# ROS-Robot-Controller.net
KiCad netlist of a schematic drawn in Altium Designer
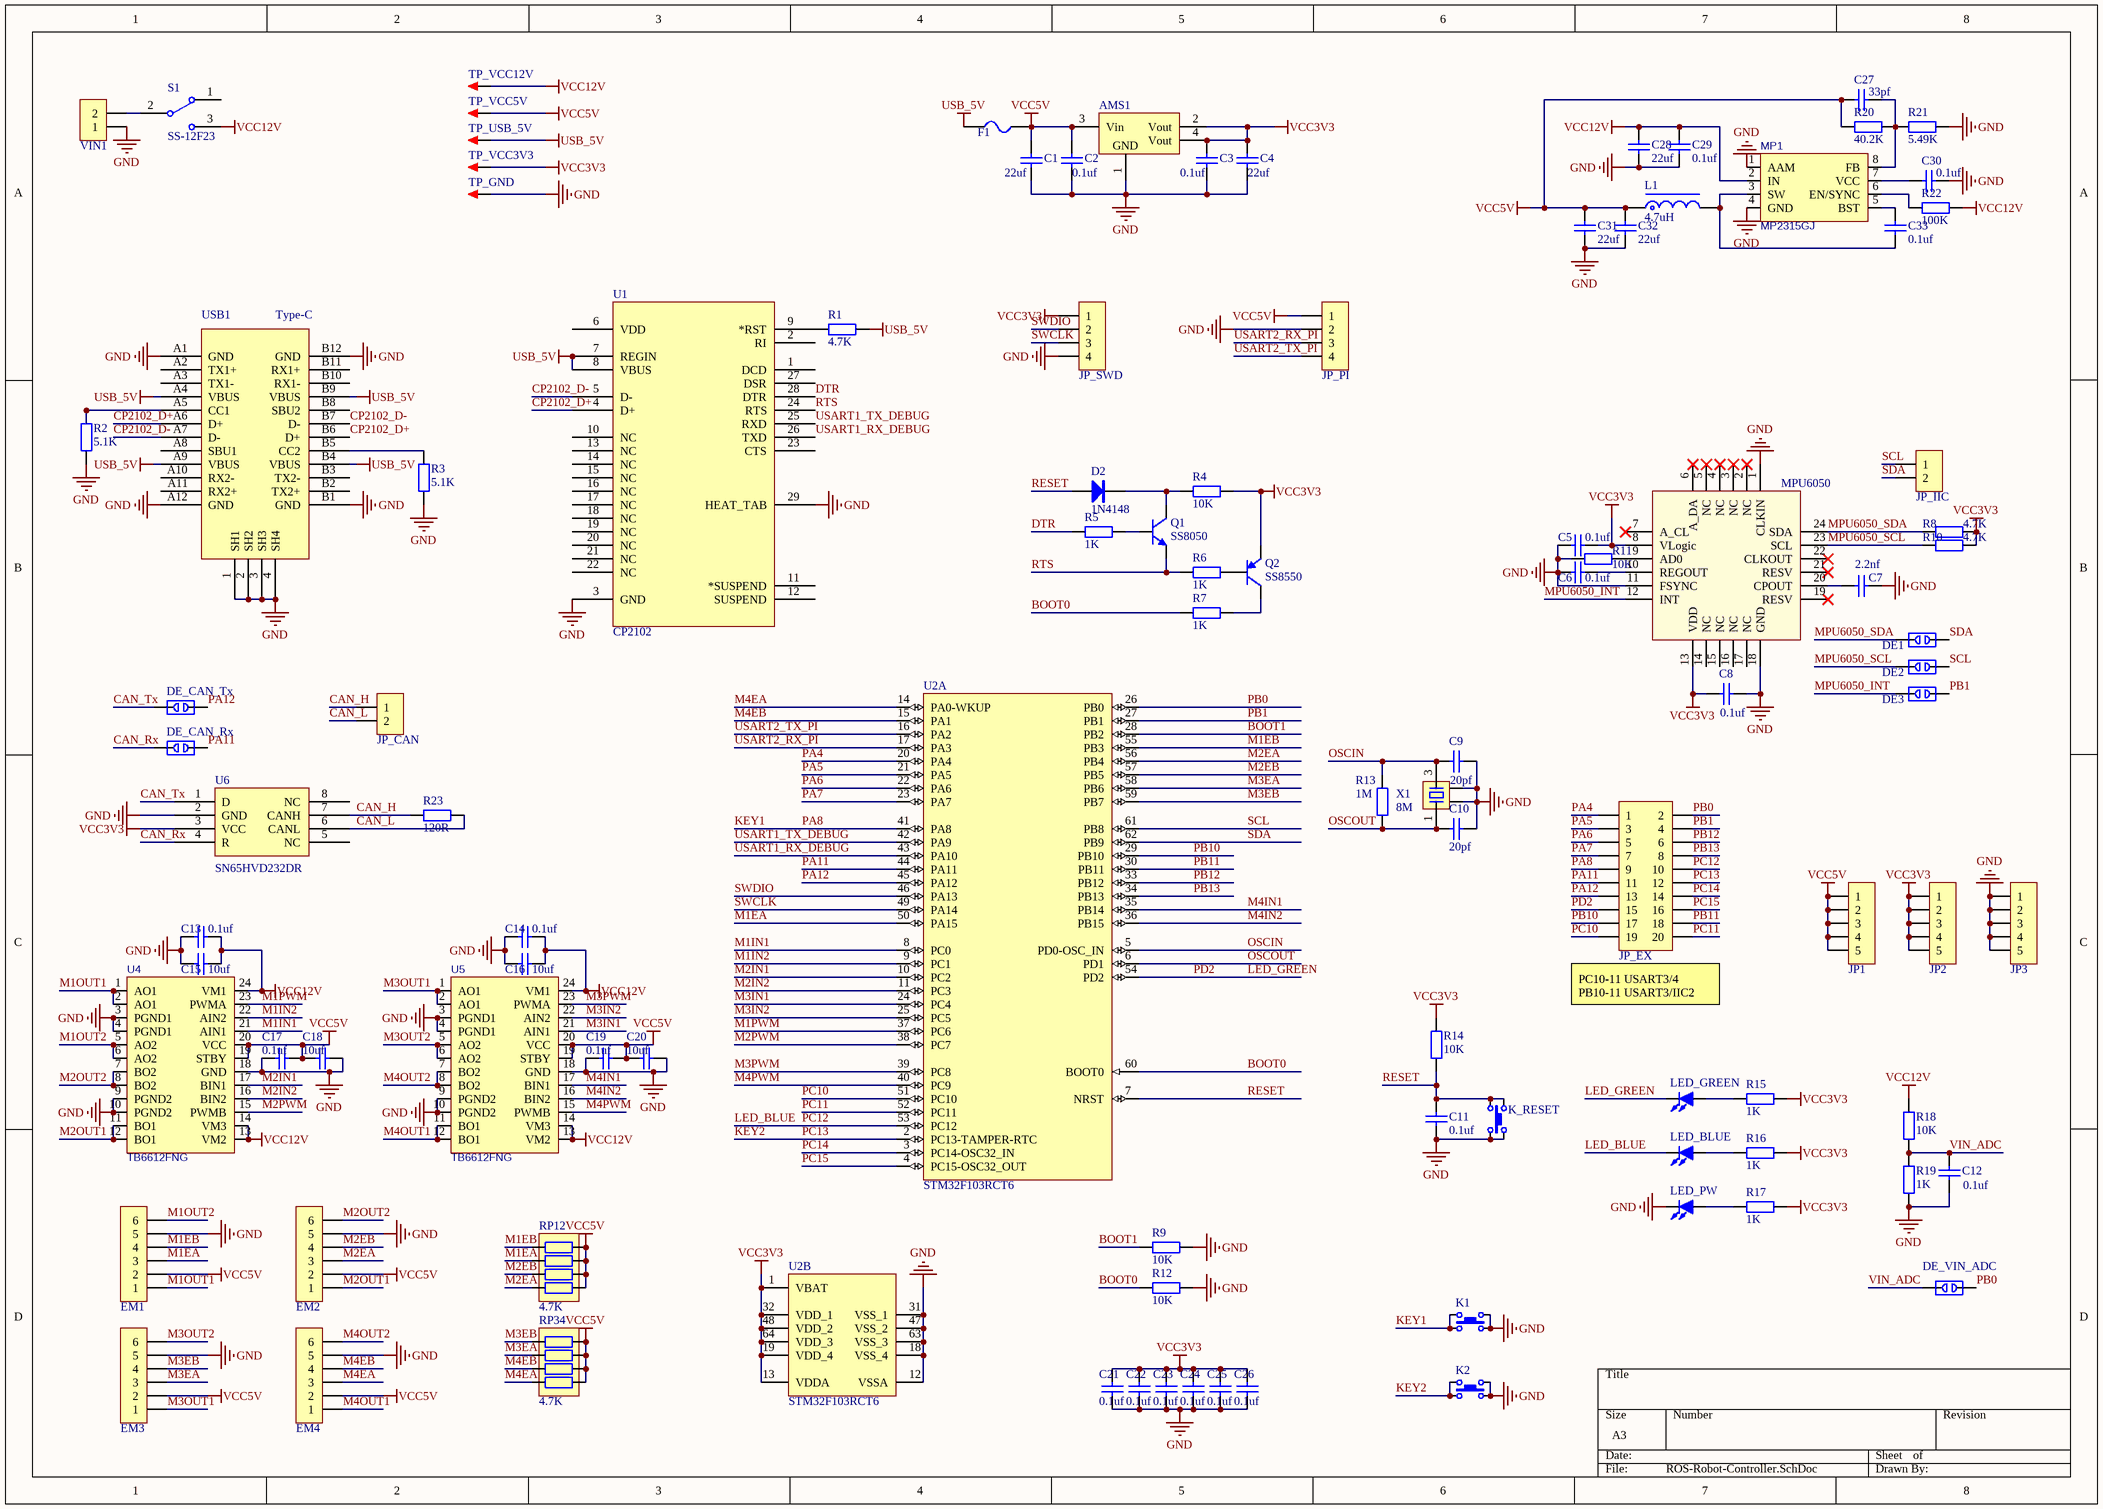
[diagram p0: ROS-Robot-Controller.SchDoc]

(export (version "E")
  (design (tool "Eeschema 10.0.6"))
  (components
    (comp (ref "AMS1")
      (value "AMS1117-3V3")
      (footprint "SOT223_L")
      (description "三端稳压芯片")
      (libsource (lib "1.1 - 电源类芯片") (part "AMS1117"))
    )
    (comp (ref "C1")
      (value "22uf")
      (footprint "C0603_L")
      (description "贴片电容")
      (libsource (lib "0.1 - 电阻-电容-电感-电位器") (part "C"))
    )
    (comp (ref "C2")
      (value "0.1uf")
      (footprint "C0603_L")
      (description "贴片电容")
      (libsource (lib "0.1 - 电阻-电容-电感-电位器") (part "C"))
    )
    (comp (ref "C3")
      (value "0.1uf")
      (footprint "C0603_L")
      (description "贴片电容")
      (libsource (lib "0.1 - 电阻-电容-电感-电位器") (part "C"))
    )
    (comp (ref "C4")
      (value "22uf")
      (footprint "C0603_L")
      (description "贴片电容")
      (libsource (lib "0.1 - 电阻-电容-电感-电位器") (part "C"))
    )
    (comp (ref "C5")
      (value "0.1uf")
      (footprint "C0402_L")
      (description "贴片电容")
      (libsource (lib "0.1 - 电阻-电容-电感-电位器") (part "C"))
    )
    (comp (ref "C6")
      (value "0.1uf")
      (footprint "C0402_L")
      (description "贴片电容")
      (libsource (lib "0.1 - 电阻-电容-电感-电位器") (part "C"))
    )
    (comp (ref "C7")
      (value "2.2nf")
      (footprint "C0402_L")
      (description "贴片电容")
      (libsource (lib "0.1 - 电阻-电容-电感-电位器") (part "C"))
    )
    (comp (ref "C8")
      (value "0.1uf")
      (footprint "C0402_L")
      (description "贴片电容")
      (libsource (lib "0.1 - 电阻-电容-电感-电位器") (part "C"))
    )
    (comp (ref "C9")
      (value "20pf")
      (footprint "C0402_L")
      (description "贴片电容")
      (libsource (lib "0.1 - 电阻-电容-电感-电位器") (part "C"))
    )
    (comp (ref "C10")
      (value "20pf")
      (footprint "C0402_L")
      (description "贴片电容")
      (libsource (lib "0.1 - 电阻-电容-电感-电位器") (part "C"))
    )
    (comp (ref "C11")
      (value "0.1uf")
      (footprint "C0402_L")
      (description "贴片电容")
      (libsource (lib "0.1 - 电阻-电容-电感-电位器") (part "C"))
    )
    (comp (ref "C12")
      (value "0.1uf")
      (footprint "C0603_L")
      (description "贴片电容")
      (libsource (lib "0.1 - 电阻-电容-电感-电位器") (part "C"))
    )
    (comp (ref "C13")
      (value "0.1uf")
      (footprint "C0603_L")
      (description "贴片电容")
      (libsource (lib "0.1 - 电阻-电容-电感-电位器") (part "C"))
    )
    (comp (ref "C14")
      (value "0.1uf")
      (footprint "C0603_L")
      (description "贴片电容")
      (libsource (lib "0.1 - 电阻-电容-电感-电位器") (part "C"))
    )
    (comp (ref "C15")
      (value "10uf")
      (footprint "C0603_L")
      (description "贴片电容")
      (libsource (lib "0.1 - 电阻-电容-电感-电位器") (part "C"))
    )
    (comp (ref "C16")
      (value "10uf")
      (footprint "C0603_L")
      (description "贴片电容")
      (libsource (lib "0.1 - 电阻-电容-电感-电位器") (part "C"))
    )
    (comp (ref "C17")
      (value "0.1uf")
      (footprint "C0402_L")
      (description "贴片电容")
      (libsource (lib "0.1 - 电阻-电容-电感-电位器") (part "C"))
    )
    (comp (ref "C18")
      (value "10uf")
      (footprint "C0402_L")
      (description "贴片电容")
      (libsource (lib "0.1 - 电阻-电容-电感-电位器") (part "C"))
    )
    (comp (ref "C19")
      (value "0.1uf")
      (footprint "C0402_L")
      (description "贴片电容")
      (libsource (lib "0.1 - 电阻-电容-电感-电位器") (part "C"))
    )
    (comp (ref "C20")
      (value "10uf")
      (footprint "C0402_L")
      (description "贴片电容")
      (libsource (lib "0.1 - 电阻-电容-电感-电位器") (part "C"))
    )
    (comp (ref "C21")
      (value "0.1uf")
      (footprint "C0402_L")
      (description "贴片电容")
      (libsource (lib "0.1 - 电阻-电容-电感-电位器") (part "C"))
    )
    (comp (ref "C22")
      (value "0.1uf")
      (footprint "C0402_L")
      (description "贴片电容")
      (libsource (lib "0.1 - 电阻-电容-电感-电位器") (part "C"))
    )
    (comp (ref "C23")
      (value "0.1uf")
      (footprint "C0402_L")
      (description "贴片电容")
      (libsource (lib "0.1 - 电阻-电容-电感-电位器") (part "C"))
    )
    (comp (ref "C24")
      (value "0.1uf")
      (footprint "C0402_L")
      (description "贴片电容")
      (libsource (lib "0.1 - 电阻-电容-电感-电位器") (part "C"))
    )
    (comp (ref "C25")
      (value "0.1uf")
      (footprint "C0402_L")
      (description "贴片电容")
      (libsource (lib "0.1 - 电阻-电容-电感-电位器") (part "C"))
    )
    (comp (ref "C26")
      (value "0.1uf")
      (footprint "C0402_L")
      (description "贴片电容")
      (libsource (lib "0.1 - 电阻-电容-电感-电位器") (part "C"))
    )
    (comp (ref "C27")
      (value "33pf")
      (footprint "C0603_L")
      (description "贴片电容")
      (libsource (lib "0.1 - 电阻-电容-电感-电位器") (part "C"))
    )
    (comp (ref "C28")
      (value "22uf")
      (footprint "C0805_L")
      (description "贴片电容")
      (libsource (lib "0.1 - 电阻-电容-电感-电位器") (part "C"))
    )
    (comp (ref "C29")
      (value "0.1uf")
      (footprint "C0805_L")
      (description "贴片电容")
      (libsource (lib "0.1 - 电阻-电容-电感-电位器") (part "C"))
    )
    (comp (ref "C30")
      (value "0.1uf")
      (footprint "C0603_L")
      (description "贴片电容")
      (libsource (lib "0.1 - 电阻-电容-电感-电位器") (part "C"))
    )
    (comp (ref "C31")
      (value "22uf")
      (footprint "C0603_L")
      (description "贴片电容")
      (libsource (lib "0.1 - 电阻-电容-电感-电位器") (part "C"))
    )
    (comp (ref "C32")
      (value "22uf")
      (footprint "C0603_L")
      (description "贴片电容")
      (libsource (lib "0.1 - 电阻-电容-电感-电位器") (part "C"))
    )
    (comp (ref "C33")
      (value "0.1uf")
      (footprint "C0603_L")
      (description "贴片电容")
      (libsource (lib "0.1 - 电阻-电容-电感-电位器") (part "C"))
    )
    (comp (ref "D2")
      (value "1N4148")
      (footprint "SOD-323")
      (description "开关二极管")
      (libsource (lib "0.2 - 二极管-TVS-整流桥") (part "1N4148"))
    )
    (comp (ref "DE1")
      (value "DEBUG PAD")
      (footprint "DEBUG_B")
      (description "调试断点焊盘")
      (libsource (lib "0.7 - 常用按键-开关-蜂鸣器-电池-测试点") (part "DEBUG"))
    )
    (comp (ref "DE2")
      (value "DEBUG PAD")
      (footprint "DEBUG_B")
      (description "调试断点焊盘")
      (libsource (lib "0.7 - 常用按键-开关-蜂鸣器-电池-测试点") (part "DEBUG"))
    )
    (comp (ref "DE3")
      (value "DEBUG PAD")
      (footprint "DEBUG_B")
      (description "调试断点焊盘")
      (libsource (lib "0.7 - 常用按键-开关-蜂鸣器-电池-测试点") (part "DEBUG"))
    )
    (comp (ref "DE_CAN_Rx")
      (value "DEBUG PAD")
      (footprint "DEBUG_B")
      (description "调试断点焊盘")
      (libsource (lib "0.7 - 常用按键-开关-蜂鸣器-电池-测试点") (part "DEBUG"))
    )
    (comp (ref "DE_CAN_Tx")
      (value "DEBUG PAD")
      (footprint "DEBUG_B")
      (description "调试断点焊盘")
      (libsource (lib "0.7 - 常用按键-开关-蜂鸣器-电池-测试点") (part "DEBUG"))
    )
    (comp (ref "DE_VIN_ADC")
      (value "DEBUG PAD")
      (footprint "DEBUG_B")
      (description "调试断点焊盘")
      (libsource (lib "0.7 - 常用按键-开关-蜂鸣器-电池-测试点") (part "DEBUG"))
    )
    (comp (ref "EM1")
      (value "HDR-1X6")
      (footprint "PH2.0-LI-6P")
      (description "6P接插件")
      (libsource (lib "5.3 - 接插件-脚距2.0") (part "Header 6"))
    )
    (comp (ref "EM2")
      (value "HDR-1X6")
      (footprint "PH2.0-LI-6P")
      (description "6P接插件")
      (libsource (lib "5.3 - 接插件-脚距2.0") (part "Header 6"))
    )
    (comp (ref "EM3")
      (value "HDR-1X6")
      (footprint "PH2.0-LI-6P")
      (description "6P接插件")
      (libsource (lib "5.3 - 接插件-脚距2.0") (part "Header 6"))
    )
    (comp (ref "EM4")
      (value "HDR-1X6")
      (footprint "PH2.0-LI-6P")
      (description "6P接插件")
      (libsource (lib "5.3 - 接插件-脚距2.0") (part "Header 6"))
    )
    (comp (ref "F1")
      (value "MSMD200-8V 2A")
      (footprint "FU 0603")
      (description "贴片保险丝")
      (libsource (lib "0.5 - 保险丝-晶振-光耦") (part "FU"))
    )
    (comp (ref "JP1")
      (value "HDR-1X5")
      (footprint "HDR2.54-LI-5P")
      (description "5P接插件")
      (libsource (lib "5.4 - 接插件-脚距2.54 (100mil) ") (part "Header 5"))
    )
    (comp (ref "JP2")
      (value "HDR-1X5")
      (footprint "HDR2.54-LI-5P")
      (description "5P接插件")
      (libsource (lib "5.4 - 接插件-脚距2.54 (100mil) ") (part "Header 5"))
    )
    (comp (ref "JP3")
      (value "HDR-1X5")
      (footprint "HDR2.54-LI-5P")
      (description "5P接插件")
      (libsource (lib "5.4 - 接插件-脚距2.54 (100mil) ") (part "Header 5"))
    )
    (comp (ref "JP_CAN")
      (value "HDR-1X2")
      (footprint "XH2.54-WI-2P")
      (description "2P接插件")
      (libsource (lib "5.4 - 接插件-脚距2.54 (100mil) ") (part "Header 2"))
    )
    (comp (ref "JP_EX")
      (value "Header 2X10")
      (footprint "IDC2.54-LI-2x10P")
      (description "10*2P接插件")
      (libsource (lib "5.4 - 接插件-脚距2.54 (100mil) ") (part "Header 10X2"))
    )
    (comp (ref "JP_IIC")
      (value "HDR-1X2")
      (footprint "XH2.54-WI-2P")
      (description "2P接插件")
      (libsource (lib "5.4 - 接插件-脚距2.54 (100mil) ") (part "Header 2"))
    )
    (comp (ref "JP_PI")
      (value "HDR-1X4")
      (footprint "HDR2.54-LI-4P")
      (description "4P接插件")
      (libsource (lib "5.4 - 接插件-脚距2.54 (100mil) ") (part "Header 4"))
    )
    (comp (ref "JP_SWD")
      (value "HDR-1X4")
      (footprint "XH2.54-WI-4P")
      (description "4P接插件")
      (libsource (lib "5.4 - 接插件-脚距2.54 (100mil) ") (part "Header 4"))
    )
    (comp (ref "K1")
      (value "TACT 4P")
      (footprint "SW-SMD_4P-L4.2-W3.3-P2.15-LS5.1")
      (description "Button")
      (libsource (lib "KitSprout") (part "ButtonTACT"))
    )
    (comp (ref "K2")
      (value "TACT 4P")
      (footprint "SW-SMD_4P-L4.2-W3.3-P2.15-LS5.1")
      (description "Button")
      (libsource (lib "KitSprout") (part "ButtonTACT"))
    )
    (comp (ref "K_RESET")
      (value "TACT 4P")
      (footprint "SW-SMD_4P-L4.2-W3.3-P2.15-LS5.1")
      (description "Button")
      (libsource (lib "KitSprout") (part "ButtonTACT"))
    )
    (comp (ref "L1")
      (value "4.7uH")
      (footprint "L-SMD-0420")
      (description "一体成型电感")
      (libsource (lib "0.1 - 电阻-电容-电感-电位器") (part "L-Molding Choke"))
    )
    (comp (ref "LED_BLUE")
      (value "红色")
      (footprint "LED_0402_RED")
      (description "贴片LED")
      (libsource (lib "0.3 - LED发光二极管") (part "LED-SMD"))
    )
    (comp (ref "LED_GREEN")
      (value "红色")
      (footprint "LED_0402_RED")
      (description "贴片LED")
      (libsource (lib "0.3 - LED发光二极管") (part "LED-SMD"))
    )
    (comp (ref "LED_PW")
      (value "红色")
      (footprint "LED_0402_RED")
      (description "贴片LED")
      (libsource (lib "0.3 - LED发光二极管") (part "LED-SMD"))
    )
    (comp (ref "MP1")
      (value "MP2315GJ")
      (footprint "SOT23-8N")
      (description "3A/24V DC-DC降压芯片")
      (libsource (lib "1.1 - 电源类芯片") (part "MP2315"))
    )
    (comp (ref "Q1")
      (value "SS8050")
      (footprint "SOT23-3N")
      (description "高频放大-NPN型")
      (libsource (lib "0.4 - 三极管-场效应管-可控硅") (part "8050-SMD"))
    )
    (comp (ref "Q2")
      (value "SS8550")
      (footprint "SOT23-3N")
      (description "高频放大-PNP型")
      (libsource (lib "0.4 - 三极管-场效应管-可控硅") (part "8550-SMD"))
    )
    (comp (ref "R1")
      (value "4.7K")
      (footprint "R0402_L")
      (description "贴片电阻")
      (libsource (lib "0.1 - 电阻-电容-电感-电位器") (part "R"))
    )
    (comp (ref "R2")
      (value "5.1K")
      (footprint "R0402_L")
      (description "贴片电阻")
      (libsource (lib "0.1 - 电阻-电容-电感-电位器") (part "R"))
    )
    (comp (ref "R3")
      (value "5.1K")
      (footprint "R0402_L")
      (description "贴片电阻")
      (libsource (lib "0.1 - 电阻-电容-电感-电位器") (part "R"))
    )
    (comp (ref "R4")
      (value "10K")
      (footprint "R0402_L")
      (description "贴片电阻")
      (libsource (lib "0.1 - 电阻-电容-电感-电位器") (part "R"))
    )
    (comp (ref "R5")
      (value "1K")
      (footprint "R0402_L")
      (description "贴片电阻")
      (libsource (lib "0.1 - 电阻-电容-电感-电位器") (part "R"))
    )
    (comp (ref "R6")
      (value "1K")
      (footprint "R0402_L")
      (description "贴片电阻")
      (libsource (lib "0.1 - 电阻-电容-电感-电位器") (part "R"))
    )
    (comp (ref "R7")
      (value "1K")
      (footprint "R0402_L")
      (description "贴片电阻")
      (libsource (lib "0.1 - 电阻-电容-电感-电位器") (part "R"))
    )
    (comp (ref "R8")
      (value "4.7K")
      (footprint "R0402_L")
      (description "贴片电阻")
      (libsource (lib "0.1 - 电阻-电容-电感-电位器") (part "R"))
    )
    (comp (ref "R9")
      (value "10K")
      (footprint "R0402_L")
      (description "贴片电阻")
      (libsource (lib "0.1 - 电阻-电容-电感-电位器") (part "R"))
    )
    (comp (ref "R10")
      (value "4.7K")
      (footprint "R0402_L")
      (description "贴片电阻")
      (libsource (lib "0.1 - 电阻-电容-电感-电位器") (part "R"))
    )
    (comp (ref "R11")
      (value "10K")
      (footprint "R0402_L")
      (description "贴片电阻")
      (libsource (lib "0.1 - 电阻-电容-电感-电位器") (part "R"))
    )
    (comp (ref "R12")
      (value "10K")
      (footprint "R0402_L")
      (description "贴片电阻")
      (libsource (lib "0.1 - 电阻-电容-电感-电位器") (part "R"))
    )
    (comp (ref "R13")
      (value "1M")
      (footprint "R0402_L")
      (description "贴片电阻")
      (libsource (lib "0.1 - 电阻-电容-电感-电位器") (part "R"))
    )
    (comp (ref "R14")
      (value "10K")
      (footprint "R0402_L")
      (description "贴片电阻")
      (libsource (lib "0.1 - 电阻-电容-电感-电位器") (part "R"))
    )
    (comp (ref "R15")
      (value "1K")
      (footprint "R0402_L")
      (description "贴片电阻")
      (libsource (lib "0.1 - 电阻-电容-电感-电位器") (part "R"))
    )
    (comp (ref "R16")
      (value "1K")
      (footprint "R0402_L")
      (description "贴片电阻")
      (libsource (lib "0.1 - 电阻-电容-电感-电位器") (part "R"))
    )
    (comp (ref "R17")
      (value "1K")
      (footprint "R0402_L")
      (description "贴片电阻")
      (libsource (lib "0.1 - 电阻-电容-电感-电位器") (part "R"))
    )
    (comp (ref "R18")
      (value "10K")
      (footprint "R0603_L")
      (description "贴片电阻")
      (libsource (lib "0.1 - 电阻-电容-电感-电位器") (part "R"))
    )
    (comp (ref "R19")
      (value "1K")
      (footprint "R0603_L")
      (description "贴片电阻")
      (libsource (lib "0.1 - 电阻-电容-电感-电位器") (part "R"))
    )
    (comp (ref "R20")
      (value "40.2K")
      (footprint "R0603_L")
      (description "贴片电阻")
      (libsource (lib "0.1 - 电阻-电容-电感-电位器") (part "R"))
    )
    (comp (ref "R21")
      (value "5.49K")
      (footprint "R0603_L")
      (description "贴片电阻")
      (libsource (lib "0.1 - 电阻-电容-电感-电位器") (part "R"))
    )
    (comp (ref "R22")
      (value "100K")
      (footprint "R0603_L")
      (description "贴片电阻")
      (libsource (lib "0.1 - 电阻-电容-电感-电位器") (part "R"))
    )
    (comp (ref "R23")
      (value "120R")
      (footprint "R0402_L")
      (description "贴片电阻")
      (libsource (lib "0.1 - 电阻-电容-电感-电位器") (part "R"))
    )
    (comp (ref "RP12")
      (value "4.7K")
      (footprint "RCA-8P4R-0402")
      (description "贴片4P排阻")
      (libsource (lib "0.1 - 电阻-电容-电感-电位器") (part "R-8P4R"))
    )
    (comp (ref "RP34")
      (value "4.7K")
      (footprint "RCA-8P4R-0402")
      (description "贴片4P排阻")
      (libsource (lib "0.1 - 电阻-电容-电感-电位器") (part "R-8P4R"))
    )
    (comp (ref "S1")
      (value "SS-12F23")
      (footprint "SS-12D10")
      (description "1路波动开关")
      (libsource (lib "0.7 - 常用按键-开关-蜂鸣器-电池-测试点") (part "SSW-1P"))
    )
    (comp (ref "TP_GND")
      (value "TEST")
      (footprint "TEST 1")
      (description "测试点")
      (libsource (lib "0.7 - 常用按键-开关-蜂鸣器-电池-测试点") (part "TEST"))
    )
    (comp (ref "TP_USB_5V")
      (value "TEST")
      (footprint "TEST 1")
      (description "测试点")
      (libsource (lib "0.7 - 常用按键-开关-蜂鸣器-电池-测试点") (part "TEST"))
    )
    (comp (ref "TP_VCC3V3")
      (value "TEST")
      (footprint "TEST 1")
      (description "测试点")
      (libsource (lib "0.7 - 常用按键-开关-蜂鸣器-电池-测试点") (part "TEST"))
    )
    (comp (ref "TP_VCC5V")
      (value "TEST")
      (footprint "TEST 1")
      (description "测试点")
      (libsource (lib "0.7 - 常用按键-开关-蜂鸣器-电池-测试点") (part "TEST"))
    )
    (comp (ref "TP_VCC12V")
      (value "TEST")
      (footprint "TEST 1")
      (description "测试点")
      (libsource (lib "0.7 - 常用按键-开关-蜂鸣器-电池-测试点") (part "TEST"))
    )
    (comp (ref "U1")
      (value "CP2102")
      (footprint "QFN-28")
      (description "USB转TTL")
      (libsource (lib "mLib") (part "CP2102"))
    )
    (comp (ref "U2")
      (value "STM32F103RCT6")
      (footprint "LQFP64_N")
      (libsource (lib "2.4 - STM32 F1系列单片机") (part "STM32F103RCT6"))
    )
    (comp (ref "U3")
      (value "MPU6050")
      (footprint "QFN-24")
      (description "六轴传感器")
      (libsource (lib "mLib") (part "MPU6050"))
    )
    (comp (ref "U4")
      (value "TB6612FNG")
      (footprint "SSOP24_M")
      (description "电机驱动")
      (libsource (lib "1.0 - 常见芯片") (part "TB6612FNG"))
    )
    (comp (ref "U5")
      (value "TB6612FNG")
      (footprint "SSOP24_M")
      (description "电机驱动")
      (libsource (lib "1.0 - 常见芯片") (part "TB6612FNG"))
    )
    (comp (ref "U6")
      (value "SN65HVD232D")
      (footprint "SO-8")
      (fields
        (field (name "MANUFACTURER") "Texas Instruments")
        (field (name "MANUFACTURER PART NUMBER") "SN65HVD232DR")
      )
      (libsource (lib "MyPcbLib") (part "SN65HVD232D"))
    )
    (comp (ref "USB1")
      (value "Type-C")
      (footprint "Type-C-TOP")
      (libsource (lib "MyPcbLib") (part "USB-Type-C-TOP"))
    )
    (comp (ref "VIN1")
      (value "HDR-1X2")
      (footprint "KF301-5.0-2P")
      (description "2P接插件")
      (libsource (lib "6.0 - 接插件-脚距5.0") (part "Header 2"))
    )
    (comp (ref "X1")
      (value "8M")
      (footprint "OSC 3225-4P")
      (description "4脚无源晶振")
      (libsource (lib "0.5 - 保险丝-晶振-光耦") (part "XTAL-4P"))
    )
  )
  (nets
    (net (code "1") (name "/BOOT0") (class "Default")
      (node (ref "R12") (pin "1") (pinfunction "1_1") (pintype "passive"))
      (node (ref "R7") (pin "2") (pinfunction "2_2") (pintype "passive"))
      (node (ref "U2") (pin "60") (pinfunction "BOOT0_60") (pintype "input"))
    )
    (net (code "2") (name "/BOOT1") (class "Default")
      (node (ref "R9") (pin "1") (pinfunction "1_1") (pintype "passive"))
      (node (ref "U2") (pin "28") (pinfunction "PB2_28") (pintype "bidirectional"))
    )
    (net (code "3") (name "/CAN_H") (class "Default")
      (node (ref "JP_CAN") (pin "1") (pinfunction "1_1") (pintype "passive"))
      (node (ref "R23") (pin "1") (pinfunction "1_1") (pintype "passive"))
      (node (ref "U6") (pin "7") (pinfunction "CANH_7") (pintype "passive"))
    )
    (net (code "4") (name "/CAN_L") (class "Default")
      (node (ref "JP_CAN") (pin "2") (pinfunction "2_2") (pintype "passive"))
      (node (ref "R23") (pin "2") (pinfunction "2_2") (pintype "passive"))
      (node (ref "U6") (pin "6") (pinfunction "CANL_6") (pintype "passive"))
    )
    (net (code "5") (name "/CAN_Rx") (class "Default")
      (node (ref "DE_CAN_Rx") (pin "1") (pinfunction "1_1") (pintype "passive"))
      (node (ref "U6") (pin "4") (pinfunction "R_4") (pintype "passive"))
    )
    (net (code "6") (name "/CAN_Tx") (class "Default")
      (node (ref "DE_CAN_Tx") (pin "1") (pinfunction "1_1") (pintype "passive"))
      (node (ref "U6") (pin "1") (pinfunction "D_1") (pintype "passive"))
    )
    (net (code "7") (name "/CP2102_D+") (class "Default")
      (node (ref "U1") (pin "4") (pinfunction "D+_4") (pintype "passive"))
      (node (ref "USB1") (pin "A6") (pinfunction "D+_A6") (pintype "passive"))
      (node (ref "USB1") (pin "B6") (pinfunction "D+_B6") (pintype "passive"))
    )
    (net (code "8") (name "/CP2102_D-") (class "Default")
      (node (ref "U1") (pin "5") (pinfunction "D-_5") (pintype "passive"))
      (node (ref "USB1") (pin "A7") (pinfunction "D-_A7") (pintype "passive"))
      (node (ref "USB1") (pin "B7") (pinfunction "D-_B7") (pintype "passive"))
    )
    (net (code "9") (name "/DTR") (class "Default")
      (node (ref "R5") (pin "1") (pinfunction "1_1") (pintype "passive"))
      (node (ref "U1") (pin "28") (pinfunction "DTR_28") (pintype "passive"))
    )
    (net (code "10") (name "/KEY1") (class "Default")
      (node (ref "JP_EX") (pin "9") (pinfunction "9_9") (pintype "passive"))
      (node (ref "K1") (pin "1") (pinfunction "1_1") (pintype "passive"))
      (node (ref "K1") (pin "3") (pinfunction "3_3") (pintype "passive"))
      (node (ref "U2") (pin "41") (pinfunction "PA8_41") (pintype "bidirectional"))
    )
    (net (code "11") (name "/KEY2") (class "Default")
      (node (ref "JP_EX") (pin "12") (pinfunction "12_12") (pintype "passive"))
      (node (ref "K2") (pin "1") (pinfunction "1_1") (pintype "passive"))
      (node (ref "K2") (pin "3") (pinfunction "3_3") (pintype "passive"))
      (node (ref "U2") (pin "2") (pinfunction "PC13-TAMPER-RTC_2") (pintype "bidirectional"))
    )
    (net (code "12") (name "/LED_BLUE") (class "Default")
      (node (ref "JP_EX") (pin "10") (pinfunction "10_10") (pintype "passive"))
      (node (ref "LED_BLUE") (pin "2") (pinfunction "K_2") (pintype "passive"))
      (node (ref "U2") (pin "53") (pinfunction "PC12_53") (pintype "bidirectional"))
    )
    (net (code "13") (name "/LED_GREEN") (class "Default")
      (node (ref "JP_EX") (pin "15") (pinfunction "15_15") (pintype "passive"))
      (node (ref "LED_GREEN") (pin "2") (pinfunction "K_2") (pintype "passive"))
      (node (ref "U2") (pin "54") (pinfunction "PD2_54") (pintype "bidirectional"))
    )
    (net (code "14") (name "/M1EA") (class "Default")
      (node (ref "EM1") (pin "3") (pinfunction "3_3") (pintype "passive"))
      (node (ref "RP12") (pin "2") (pinfunction "2_2") (pintype "passive"))
      (node (ref "U2") (pin "50") (pinfunction "PA15_50") (pintype "bidirectional"))
    )
    (net (code "15") (name "/M1EB") (class "Default")
      (node (ref "EM1") (pin "4") (pinfunction "4_4") (pintype "passive"))
      (node (ref "RP12") (pin "1") (pinfunction "1_1") (pintype "passive"))
      (node (ref "U2") (pin "55") (pinfunction "PB3_55") (pintype "bidirectional"))
    )
    (net (code "16") (name "/M1IN1") (class "Default")
      (node (ref "U2") (pin "8") (pinfunction "PC0_8") (pintype "bidirectional"))
      (node (ref "U4") (pin "21") (pinfunction "AIN1_21") (pintype "passive"))
    )
    (net (code "17") (name "/M1IN2") (class "Default")
      (node (ref "U2") (pin "9") (pinfunction "PC1_9") (pintype "bidirectional"))
      (node (ref "U4") (pin "22") (pinfunction "AIN2_22") (pintype "passive"))
    )
    (net (code "18") (name "/M1OUT1") (class "Default")
      (node (ref "EM1") (pin "1") (pinfunction "1_1") (pintype "passive"))
      (node (ref "U4") (pin "1") (pinfunction "AO1_1") (pintype "passive"))
      (node (ref "U4") (pin "2") (pinfunction "AO1_2") (pintype "passive"))
    )
    (net (code "19") (name "/M1OUT2") (class "Default")
      (node (ref "EM1") (pin "6") (pinfunction "6_6") (pintype "passive"))
      (node (ref "U4") (pin "5") (pinfunction "AO2_5") (pintype "passive"))
      (node (ref "U4") (pin "6") (pinfunction "AO2_6") (pintype "passive"))
    )
    (net (code "20") (name "/M1PWM") (class "Default")
      (node (ref "U2") (pin "37") (pinfunction "PC6_37") (pintype "bidirectional"))
      (node (ref "U4") (pin "23") (pinfunction "PWMA_23") (pintype "passive"))
    )
    (net (code "21") (name "/M2EA") (class "Default")
      (node (ref "EM2") (pin "3") (pinfunction "3_3") (pintype "passive"))
      (node (ref "RP12") (pin "4") (pinfunction "4_4") (pintype "passive"))
      (node (ref "U2") (pin "56") (pinfunction "PB4_56") (pintype "bidirectional"))
    )
    (net (code "22") (name "/M2EB") (class "Default")
      (node (ref "EM2") (pin "4") (pinfunction "4_4") (pintype "passive"))
      (node (ref "RP12") (pin "3") (pinfunction "3_3") (pintype "passive"))
      (node (ref "U2") (pin "57") (pinfunction "PB5_57") (pintype "bidirectional"))
    )
    (net (code "23") (name "/M2IN1") (class "Default")
      (node (ref "U2") (pin "10") (pinfunction "PC2_10") (pintype "bidirectional"))
      (node (ref "U4") (pin "17") (pinfunction "BIN1_17") (pintype "passive"))
    )
    (net (code "24") (name "/M2IN2") (class "Default")
      (node (ref "U2") (pin "11") (pinfunction "PC3_11") (pintype "bidirectional"))
      (node (ref "U4") (pin "16") (pinfunction "BIN2_16") (pintype "passive"))
    )
    (net (code "25") (name "/M2OUT1") (class "Default")
      (node (ref "EM2") (pin "1") (pinfunction "1_1") (pintype "passive"))
      (node (ref "U4") (pin "11") (pinfunction "BO1_11") (pintype "passive"))
      (node (ref "U4") (pin "12") (pinfunction "BO1_12") (pintype "passive"))
    )
    (net (code "26") (name "/M2OUT2") (class "Default")
      (node (ref "EM2") (pin "6") (pinfunction "6_6") (pintype "passive"))
      (node (ref "U4") (pin "7") (pinfunction "BO2_7") (pintype "passive"))
      (node (ref "U4") (pin "8") (pinfunction "BO2_8") (pintype "passive"))
    )
    (net (code "27") (name "/M2PWM") (class "Default")
      (node (ref "U2") (pin "38") (pinfunction "PC7_38") (pintype "bidirectional"))
      (node (ref "U4") (pin "15") (pinfunction "PWMB_15") (pintype "passive"))
    )
    (net (code "28") (name "/M3EA") (class "Default")
      (node (ref "EM3") (pin "3") (pinfunction "3_3") (pintype "passive"))
      (node (ref "RP34") (pin "2") (pinfunction "2_2") (pintype "passive"))
      (node (ref "U2") (pin "58") (pinfunction "PB6_58") (pintype "bidirectional"))
    )
    (net (code "29") (name "/M3EB") (class "Default")
      (node (ref "EM3") (pin "4") (pinfunction "4_4") (pintype "passive"))
      (node (ref "RP34") (pin "1") (pinfunction "1_1") (pintype "passive"))
      (node (ref "U2") (pin "59") (pinfunction "PB7_59") (pintype "bidirectional"))
    )
    (net (code "30") (name "/M3IN1") (class "Default")
      (node (ref "U2") (pin "24") (pinfunction "PC4_24") (pintype "bidirectional"))
      (node (ref "U5") (pin "21") (pinfunction "AIN1_21") (pintype "passive"))
    )
    (net (code "31") (name "/M3IN2") (class "Default")
      (node (ref "U2") (pin "25") (pinfunction "PC5_25") (pintype "bidirectional"))
      (node (ref "U5") (pin "22") (pinfunction "AIN2_22") (pintype "passive"))
    )
    (net (code "32") (name "/M3OUT1") (class "Default")
      (node (ref "EM3") (pin "1") (pinfunction "1_1") (pintype "passive"))
      (node (ref "U5") (pin "1") (pinfunction "AO1_1") (pintype "passive"))
      (node (ref "U5") (pin "2") (pinfunction "AO1_2") (pintype "passive"))
    )
    (net (code "33") (name "/M3OUT2") (class "Default")
      (node (ref "EM3") (pin "6") (pinfunction "6_6") (pintype "passive"))
      (node (ref "U5") (pin "5") (pinfunction "AO2_5") (pintype "passive"))
      (node (ref "U5") (pin "6") (pinfunction "AO2_6") (pintype "passive"))
    )
    (net (code "34") (name "/M3PWM") (class "Default")
      (node (ref "U2") (pin "39") (pinfunction "PC8_39") (pintype "bidirectional"))
      (node (ref "U5") (pin "23") (pinfunction "PWMA_23") (pintype "passive"))
    )
    (net (code "35") (name "/M4EA") (class "Default")
      (node (ref "EM4") (pin "3") (pinfunction "3_3") (pintype "passive"))
      (node (ref "RP34") (pin "4") (pinfunction "4_4") (pintype "passive"))
      (node (ref "U2") (pin "14") (pinfunction "PA0-WKUP_14") (pintype "bidirectional"))
    )
    (net (code "36") (name "/M4EB") (class "Default")
      (node (ref "EM4") (pin "4") (pinfunction "4_4") (pintype "passive"))
      (node (ref "RP34") (pin "3") (pinfunction "3_3") (pintype "passive"))
      (node (ref "U2") (pin "15") (pinfunction "PA1_15") (pintype "bidirectional"))
    )
    (net (code "37") (name "/M4IN1") (class "Default")
      (node (ref "U2") (pin "35") (pinfunction "PB14_35") (pintype "bidirectional"))
      (node (ref "U5") (pin "17") (pinfunction "BIN1_17") (pintype "passive"))
    )
    (net (code "38") (name "/M4IN2") (class "Default")
      (node (ref "U2") (pin "36") (pinfunction "PB15_36") (pintype "bidirectional"))
      (node (ref "U5") (pin "16") (pinfunction "BIN2_16") (pintype "passive"))
    )
    (net (code "39") (name "/M4OUT1") (class "Default")
      (node (ref "EM4") (pin "1") (pinfunction "1_1") (pintype "passive"))
      (node (ref "U5") (pin "11") (pinfunction "BO1_11") (pintype "passive"))
      (node (ref "U5") (pin "12") (pinfunction "BO1_12") (pintype "passive"))
    )
    (net (code "40") (name "/M4OUT2") (class "Default")
      (node (ref "EM4") (pin "6") (pinfunction "6_6") (pintype "passive"))
      (node (ref "U5") (pin "7") (pinfunction "BO2_7") (pintype "passive"))
      (node (ref "U5") (pin "8") (pinfunction "BO2_8") (pintype "passive"))
    )
    (net (code "41") (name "/M4PWM") (class "Default")
      (node (ref "U2") (pin "40") (pinfunction "PC9_40") (pintype "bidirectional"))
      (node (ref "U5") (pin "15") (pinfunction "PWMB_15") (pintype "passive"))
    )
    (net (code "42") (name "/MPU6050_INT") (class "Default")
      (node (ref "DE3") (pin "1") (pinfunction "1_1") (pintype "passive"))
      (node (ref "U3") (pin "12") (pinfunction "INT_12") (pintype "passive"))
    )
    (net (code "43") (name "/MPU6050_SCL") (class "Default")
      (node (ref "DE2") (pin "1") (pinfunction "1_1") (pintype "passive"))
      (node (ref "R10") (pin "1") (pinfunction "1_1") (pintype "passive"))
      (node (ref "U3") (pin "23") (pinfunction "SCL_23") (pintype "passive"))
    )
    (net (code "44") (name "/MPU6050_SDA") (class "Default")
      (node (ref "DE1") (pin "1") (pinfunction "1_1") (pintype "passive"))
      (node (ref "R8") (pin "1") (pinfunction "1_1") (pintype "passive"))
      (node (ref "U3") (pin "24") (pinfunction "SDA_24") (pintype "passive"))
    )
    (net (code "45") (name "/OSCIN") (class "Default")
      (node (ref "C9") (pin "1") (pinfunction "1_1") (pintype "passive"))
      (node (ref "R13") (pin "2") (pinfunction "2_2") (pintype "passive"))
      (node (ref "U2") (pin "5") (pinfunction "PD0-OSC_IN_5") (pintype "bidirectional"))
      (node (ref "X1") (pin "3") (pinfunction "3_3") (pintype "passive"))
    )
    (net (code "46") (name "/OSCOUT") (class "Default")
      (node (ref "C10") (pin "1") (pinfunction "1_1") (pintype "passive"))
      (node (ref "R13") (pin "1") (pinfunction "1_1") (pintype "passive"))
      (node (ref "U2") (pin "6") (pinfunction "PD1_6") (pintype "bidirectional"))
      (node (ref "X1") (pin "1") (pinfunction "1_1") (pintype "passive"))
    )
    (net (code "47") (name "/PA4") (class "Default")
      (node (ref "JP_EX") (pin "1") (pinfunction "1_1") (pintype "passive"))
      (node (ref "U2") (pin "20") (pinfunction "PA4_20") (pintype "bidirectional"))
    )
    (net (code "48") (name "/PA5") (class "Default")
      (node (ref "JP_EX") (pin "3") (pinfunction "3_3") (pintype "passive"))
      (node (ref "U2") (pin "21") (pinfunction "PA5_21") (pintype "bidirectional"))
    )
    (net (code "49") (name "/PA6") (class "Default")
      (node (ref "JP_EX") (pin "5") (pinfunction "5_5") (pintype "passive"))
      (node (ref "U2") (pin "22") (pinfunction "PA6_22") (pintype "bidirectional"))
    )
    (net (code "50") (name "/PA7") (class "Default")
      (node (ref "JP_EX") (pin "7") (pinfunction "7_7") (pintype "passive"))
      (node (ref "U2") (pin "23") (pinfunction "PA7_23") (pintype "bidirectional"))
    )
    (net (code "51") (name "/PA11") (class "Default")
      (node (ref "DE_CAN_Rx") (pin "2") (pinfunction "2_2") (pintype "passive"))
      (node (ref "JP_EX") (pin "11") (pinfunction "11_11") (pintype "passive"))
      (node (ref "U2") (pin "44") (pinfunction "PA11_44") (pintype "bidirectional"))
    )
    (net (code "52") (name "/PA12") (class "Default")
      (node (ref "DE_CAN_Tx") (pin "2") (pinfunction "2_2") (pintype "passive"))
      (node (ref "JP_EX") (pin "13") (pinfunction "13_13") (pintype "passive"))
      (node (ref "U2") (pin "45") (pinfunction "PA12_45") (pintype "bidirectional"))
    )
    (net (code "53") (name "/PB0") (class "Default")
      (node (ref "DE_VIN_ADC") (pin "2") (pinfunction "2_2") (pintype "passive"))
      (node (ref "JP_EX") (pin "2") (pinfunction "2_2") (pintype "passive"))
      (node (ref "U2") (pin "26") (pinfunction "PB0_26") (pintype "bidirectional"))
    )
    (net (code "54") (name "/PB1") (class "Default")
      (node (ref "DE3") (pin "2") (pinfunction "2_2") (pintype "passive"))
      (node (ref "JP_EX") (pin "4") (pinfunction "4_4") (pintype "passive"))
      (node (ref "U2") (pin "27") (pinfunction "PB1_27") (pintype "bidirectional"))
    )
    (net (code "55") (name "/PB10") (class "Default")
      (node (ref "JP_EX") (pin "17") (pinfunction "17_17") (pintype "passive"))
      (node (ref "U2") (pin "29") (pinfunction "PB10_29") (pintype "bidirectional"))
    )
    (net (code "56") (name "/PB11") (class "Default")
      (node (ref "JP_EX") (pin "18") (pinfunction "18_18") (pintype "passive"))
      (node (ref "U2") (pin "30") (pinfunction "PB11_30") (pintype "bidirectional"))
    )
    (net (code "57") (name "/PB12") (class "Default")
      (node (ref "JP_EX") (pin "6") (pinfunction "6_6") (pintype "passive"))
      (node (ref "U2") (pin "33") (pinfunction "PB12_33") (pintype "bidirectional"))
    )
    (net (code "58") (name "/PB13") (class "Default")
      (node (ref "JP_EX") (pin "8") (pinfunction "8_8") (pintype "passive"))
      (node (ref "U2") (pin "34") (pinfunction "PB13_34") (pintype "bidirectional"))
    )
    (net (code "59") (name "/PC10") (class "Default")
      (node (ref "JP_EX") (pin "19") (pinfunction "19_19") (pintype "passive"))
      (node (ref "U2") (pin "51") (pinfunction "PC10_51") (pintype "bidirectional"))
    )
    (net (code "60") (name "/PC11") (class "Default")
      (node (ref "JP_EX") (pin "20") (pinfunction "20_20") (pintype "passive"))
      (node (ref "U2") (pin "52") (pinfunction "PC11_52") (pintype "bidirectional"))
    )
    (net (code "61") (name "/PC14") (class "Default")
      (node (ref "JP_EX") (pin "14") (pinfunction "14_14") (pintype "passive"))
      (node (ref "U2") (pin "3") (pinfunction "PC14-OSC32_IN_3") (pintype "bidirectional"))
    )
    (net (code "62") (name "/PC15") (class "Default")
      (node (ref "JP_EX") (pin "16") (pinfunction "16_16") (pintype "passive"))
      (node (ref "U2") (pin "4") (pinfunction "PC15-OSC32_OUT_4") (pintype "bidirectional"))
    )
    (net (code "63") (name "/RESET") (class "Default")
      (node (ref "C11") (pin "2") (pinfunction "2_2") (pintype "passive"))
      (node (ref "D2") (pin "1") (pinfunction "A_1") (pintype "passive"))
      (node (ref "K_RESET") (pin "1") (pinfunction "1_1") (pintype "passive"))
      (node (ref "K_RESET") (pin "3") (pinfunction "3_3") (pintype "passive"))
      (node (ref "R14") (pin "1") (pinfunction "1_1") (pintype "passive"))
      (node (ref "U2") (pin "7") (pinfunction "NRST_7") (pintype "bidirectional"))
    )
    (net (code "64") (name "/RTS") (class "Default")
      (node (ref "Q1") (pin "2") (pinfunction "E_2") (pintype "passive"))
      (node (ref "R6") (pin "1") (pinfunction "1_1") (pintype "passive"))
      (node (ref "U1") (pin "24") (pinfunction "RTS_24") (pintype "passive"))
    )
    (net (code "65") (name "/SCL") (class "Default")
      (node (ref "DE2") (pin "2") (pinfunction "2_2") (pintype "passive"))
      (node (ref "JP_IIC") (pin "1") (pinfunction "1_1") (pintype "passive"))
      (node (ref "U2") (pin "61") (pinfunction "PB8_61") (pintype "bidirectional"))
    )
    (net (code "66") (name "/SDA") (class "Default")
      (node (ref "DE1") (pin "2") (pinfunction "2_2") (pintype "passive"))
      (node (ref "JP_IIC") (pin "2") (pinfunction "2_2") (pintype "passive"))
      (node (ref "U2") (pin "62") (pinfunction "PB9_62") (pintype "bidirectional"))
    )
    (net (code "67") (name "/SWCLK") (class "Default")
      (node (ref "JP_SWD") (pin "3") (pinfunction "3_3") (pintype "passive"))
      (node (ref "U2") (pin "49") (pinfunction "PA14_49") (pintype "bidirectional"))
    )
    (net (code "68") (name "/SWDIO") (class "Default")
      (node (ref "JP_SWD") (pin "2") (pinfunction "2_2") (pintype "passive"))
      (node (ref "U2") (pin "46") (pinfunction "PA13_46") (pintype "bidirectional"))
    )
    (net (code "69") (name "/USART1_RX_DEBUG") (class "Default")
      (node (ref "U1") (pin "26") (pinfunction "TXD_26") (pintype "passive"))
      (node (ref "U2") (pin "43") (pinfunction "PA10_43") (pintype "bidirectional"))
    )
    (net (code "70") (name "/USART1_TX_DEBUG") (class "Default")
      (node (ref "U1") (pin "25") (pinfunction "RXD_25") (pintype "passive"))
      (node (ref "U2") (pin "42") (pinfunction "PA9_42") (pintype "bidirectional"))
    )
    (net (code "71") (name "/USART2_RX_PI") (class "Default")
      (node (ref "JP_PI") (pin "3") (pinfunction "3_3") (pintype "passive"))
      (node (ref "U2") (pin "17") (pinfunction "PA3_17") (pintype "bidirectional"))
    )
    (net (code "72") (name "/USART2_TX_PI") (class "Default")
      (node (ref "JP_PI") (pin "4") (pinfunction "4_4") (pintype "passive"))
      (node (ref "U2") (pin "16") (pinfunction "PA2_16") (pintype "bidirectional"))
    )
    (net (code "73") (name "/VIN_ADC") (class "Default")
      (node (ref "C12") (pin "2") (pinfunction "2_2") (pintype "passive"))
      (node (ref "DE_VIN_ADC") (pin "1") (pinfunction "1_1") (pintype "passive"))
      (node (ref "R18") (pin "1") (pinfunction "1_1") (pintype "passive"))
      (node (ref "R19") (pin "2") (pinfunction "2_2") (pintype "passive"))
    )
    (net (code "74") (name "GND") (class "Default")
      (node (ref "AMS1") (pin "1") (pinfunction "GND_1") (pintype "passive"))
      (node (ref "C1") (pin "1") (pinfunction "1_1") (pintype "passive"))
      (node (ref "C10") (pin "2") (pinfunction "2_2") (pintype "passive"))
      (node (ref "C11") (pin "1") (pinfunction "1_1") (pintype "passive"))
      (node (ref "C12") (pin "1") (pinfunction "1_1") (pintype "passive"))
      (node (ref "C13") (pin "1") (pinfunction "1_1") (pintype "passive"))
      (node (ref "C14") (pin "1") (pinfunction "1_1") (pintype "passive"))
      (node (ref "C15") (pin "1") (pinfunction "1_1") (pintype "passive"))
      (node (ref "C16") (pin "1") (pinfunction "1_1") (pintype "passive"))
      (node (ref "C17") (pin "2") (pinfunction "2_2") (pintype "passive"))
      (node (ref "C18") (pin "1") (pinfunction "1_1") (pintype "passive"))
      (node (ref "C19") (pin "2") (pinfunction "2_2") (pintype "passive"))
      (node (ref "C2") (pin "1") (pinfunction "1_1") (pintype "passive"))
      (node (ref "C20") (pin "1") (pinfunction "1_1") (pintype "passive"))
      (node (ref "C21") (pin "1") (pinfunction "1_1") (pintype "passive"))
      (node (ref "C22") (pin "1") (pinfunction "1_1") (pintype "passive"))
      (node (ref "C23") (pin "1") (pinfunction "1_1") (pintype "passive"))
      (node (ref "C24") (pin "1") (pinfunction "1_1") (pintype "passive"))
      (node (ref "C25") (pin "1") (pinfunction "1_1") (pintype "passive"))
      (node (ref "C26") (pin "1") (pinfunction "1_1") (pintype "passive"))
      (node (ref "C28") (pin "1") (pinfunction "1_1") (pintype "passive"))
      (node (ref "C29") (pin "1") (pinfunction "1_1") (pintype "passive"))
      (node (ref "C3") (pin "1") (pinfunction "1_1") (pintype "passive"))
      (node (ref "C30") (pin "1") (pinfunction "1_1") (pintype "passive"))
      (node (ref "C31") (pin "1") (pinfunction "1_1") (pintype "passive"))
      (node (ref "C32") (pin "1") (pinfunction "1_1") (pintype "passive"))
      (node (ref "C4") (pin "1") (pinfunction "1_1") (pintype "passive"))
      (node (ref "C5") (pin "1") (pinfunction "1_1") (pintype "passive"))
      (node (ref "C6") (pin "1") (pinfunction "1_1") (pintype "passive"))
      (node (ref "C7") (pin "2") (pinfunction "2_2") (pintype "passive"))
      (node (ref "C8") (pin "2") (pinfunction "2_2") (pintype "passive"))
      (node (ref "C9") (pin "2") (pinfunction "2_2") (pintype "passive"))
      (node (ref "EM1") (pin "5") (pinfunction "5_5") (pintype "passive"))
      (node (ref "EM2") (pin "5") (pinfunction "5_5") (pintype "passive"))
      (node (ref "EM3") (pin "5") (pinfunction "5_5") (pintype "passive"))
      (node (ref "EM4") (pin "5") (pinfunction "5_5") (pintype "passive"))
      (node (ref "JP3") (pin "1") (pinfunction "1_1") (pintype "passive"))
      (node (ref "JP3") (pin "2") (pinfunction "2_2") (pintype "passive"))
      (node (ref "JP3") (pin "3") (pinfunction "3_3") (pintype "passive"))
      (node (ref "JP3") (pin "4") (pinfunction "4_4") (pintype "passive"))
      (node (ref "JP3") (pin "5") (pinfunction "5_5") (pintype "passive"))
      (node (ref "JP_PI") (pin "2") (pinfunction "2_2") (pintype "passive"))
      (node (ref "JP_SWD") (pin "4") (pinfunction "4_4") (pintype "passive"))
      (node (ref "K1") (pin "2") (pinfunction "2_2") (pintype "passive"))
      (node (ref "K1") (pin "4") (pinfunction "4_4") (pintype "passive"))
      (node (ref "K2") (pin "2") (pinfunction "2_2") (pintype "passive"))
      (node (ref "K2") (pin "4") (pinfunction "4_4") (pintype "passive"))
      (node (ref "K_RESET") (pin "2") (pinfunction "2_2") (pintype "passive"))
      (node (ref "K_RESET") (pin "4") (pinfunction "4_4") (pintype "passive"))
      (node (ref "LED_PW") (pin "2") (pinfunction "K_2") (pintype "passive"))
      (node (ref "MP1") (pin "1") (pinfunction "AAM_1") (pintype "passive"))
      (node (ref "MP1") (pin "4") (pinfunction "GND_4") (pintype "passive"))
      (node (ref "R11") (pin "1") (pinfunction "1_1") (pintype "passive"))
      (node (ref "R12") (pin "2") (pinfunction "2_2") (pintype "passive"))
      (node (ref "R19") (pin "1") (pinfunction "1_1") (pintype "passive"))
      (node (ref "R2") (pin "1") (pinfunction "1_1") (pintype "passive"))
      (node (ref "R21") (pin "2") (pinfunction "2_2") (pintype "passive"))
      (node (ref "R3") (pin "1") (pinfunction "1_1") (pintype "passive"))
      (node (ref "R9") (pin "2") (pinfunction "2_2") (pintype "passive"))
      (node (ref "TP_GND") (pin "1") (pinfunction "1_1") (pintype "passive"))
      (node (ref "U1") (pin "29") (pinfunction "HEAT_TAB_29") (pintype "passive"))
      (node (ref "U1") (pin "3") (pinfunction "GND_3") (pintype "passive"))
      (node (ref "U2") (pin "12") (pinfunction "VSSA_12") (pintype "power_in"))
      (node (ref "U2") (pin "18") (pinfunction "VSS_4_18") (pintype "power_in"))
      (node (ref "U2") (pin "31") (pinfunction "VSS_1_31") (pintype "power_in"))
      (node (ref "U2") (pin "47") (pinfunction "VSS_2_47") (pintype "power_in"))
      (node (ref "U2") (pin "63") (pinfunction "VSS_3_63") (pintype "power_in"))
      (node (ref "U3") (pin "1") (pinfunction "CLKIN_1") (pintype "passive"))
      (node (ref "U3") (pin "11") (pinfunction "FSYNC_11") (pintype "passive"))
      (node (ref "U3") (pin "18") (pinfunction "GND_18") (pintype "passive"))
      (node (ref "U4") (pin "10") (pinfunction "PGND2_10") (pintype "passive"))
      (node (ref "U4") (pin "18") (pinfunction "GND_18") (pintype "passive"))
      (node (ref "U4") (pin "3") (pinfunction "PGND1_3") (pintype "passive"))
      (node (ref "U4") (pin "4") (pinfunction "PGND1_4") (pintype "passive"))
      (node (ref "U4") (pin "9") (pinfunction "PGND2_9") (pintype "passive"))
      (node (ref "U5") (pin "10") (pinfunction "PGND2_10") (pintype "passive"))
      (node (ref "U5") (pin "18") (pinfunction "GND_18") (pintype "passive"))
      (node (ref "U5") (pin "3") (pinfunction "PGND1_3") (pintype "passive"))
      (node (ref "U5") (pin "4") (pinfunction "PGND1_4") (pintype "passive"))
      (node (ref "U5") (pin "9") (pinfunction "PGND2_9") (pintype "passive"))
      (node (ref "U6") (pin "2") (pinfunction "GND_2") (pintype "passive"))
      (node (ref "USB1") (pin "1") (pinfunction "SH1_1") (pintype "passive"))
      (node (ref "USB1") (pin "2") (pinfunction "SH2_2") (pintype "passive"))
      (node (ref "USB1") (pin "3") (pinfunction "SH3_3") (pintype "passive"))
      (node (ref "USB1") (pin "4") (pinfunction "SH4_4") (pintype "passive"))
      (node (ref "USB1") (pin "A1") (pinfunction "GND_A1") (pintype "passive"))
      (node (ref "USB1") (pin "A12") (pinfunction "GND_A12") (pintype "passive"))
      (node (ref "USB1") (pin "B1") (pinfunction "GND_B1") (pintype "passive"))
      (node (ref "USB1") (pin "B12") (pinfunction "GND_B12") (pintype "passive"))
      (node (ref "VIN1") (pin "1") (pinfunction "1_1") (pintype "passive"))
      (node (ref "X1") (pin "2") (pinfunction "2_2") (pintype "passive"))
      (node (ref "X1") (pin "4") (pinfunction "4_4") (pintype "passive"))
    )
    (net (code "75") (name "Net-(D2-K)") (class "Default")
      (node (ref "D2") (pin "2") (pinfunction "K_2") (pintype "passive"))
      (node (ref "Q1") (pin "3") (pinfunction "C_3") (pintype "passive"))
      (node (ref "R4") (pin "2") (pinfunction "2_2") (pintype "passive"))
    )
    (net (code "76") (name "Net-(LED_BLUE-A)") (class "Default")
      (node (ref "LED_BLUE") (pin "1") (pinfunction "A_1") (pintype "passive"))
      (node (ref "R16") (pin "1") (pinfunction "1_1") (pintype "passive"))
    )
    (net (code "77") (name "Net-(LED_GREEN-A)") (class "Default")
      (node (ref "LED_GREEN") (pin "1") (pinfunction "A_1") (pintype "passive"))
      (node (ref "R15") (pin "1") (pinfunction "1_1") (pintype "passive"))
    )
    (net (code "78") (name "Net-(LED_PW-A)") (class "Default")
      (node (ref "LED_PW") (pin "1") (pinfunction "A_1") (pintype "passive"))
      (node (ref "R17") (pin "1") (pinfunction "1_1") (pintype "passive"))
    )
    (net (code "79") (name "Net-(MP1-BST)") (class "Default")
      (node (ref "C33") (pin "2") (pinfunction "2_2") (pintype "passive"))
      (node (ref "MP1") (pin "5") (pinfunction "BST_5") (pintype "passive"))
    )
    (net (code "80") (name "Net-(MP1-EN{slash}SYNC)") (class "Default")
      (node (ref "MP1") (pin "6") (pinfunction "EN/SYNC_6") (pintype "passive"))
      (node (ref "R22") (pin "1") (pinfunction "1_1") (pintype "passive"))
    )
    (net (code "81") (name "Net-(MP1-FB)") (class "Default")
      (node (ref "C27") (pin "1") (pinfunction "1_1") (pintype "passive"))
      (node (ref "MP1") (pin "8") (pinfunction "FB_8") (pintype "passive"))
      (node (ref "R20") (pin "2") (pinfunction "2_2") (pintype "passive"))
      (node (ref "R21") (pin "1") (pinfunction "1_1") (pintype "passive"))
    )
    (net (code "82") (name "Net-(MP1-SW)") (class "Default")
      (node (ref "C33") (pin "1") (pinfunction "1_1") (pintype "passive"))
      (node (ref "L1") (pin "2") (pinfunction "2_2") (pintype "passive"))
      (node (ref "MP1") (pin "3") (pinfunction "SW_3") (pintype "passive"))
    )
    (net (code "83") (name "Net-(MP1-VCC)") (class "Default")
      (node (ref "C30") (pin "2") (pinfunction "2_2") (pintype "passive"))
      (node (ref "MP1") (pin "7") (pinfunction "VCC_7") (pintype "passive"))
    )
    (net (code "84") (name "Net-(Q1-B)") (class "Default")
      (node (ref "Q1") (pin "1") (pinfunction "B_1") (pintype "passive"))
      (node (ref "R5") (pin "2") (pinfunction "2_2") (pintype "passive"))
    )
    (net (code "85") (name "Net-(Q2-B)") (class "Default")
      (node (ref "Q2") (pin "1") (pinfunction "B_1") (pintype "passive"))
      (node (ref "R6") (pin "2") (pinfunction "2_2") (pintype "passive"))
    )
    (net (code "86") (name "Net-(Q2-C)") (class "Default")
      (node (ref "Q2") (pin "3") (pinfunction "C_3") (pintype "passive"))
      (node (ref "R7") (pin "1") (pinfunction "1_1") (pintype "passive"))
    )
    (net (code "87") (name "Net-(S1-Pad2)") (class "Default")
      (node (ref "S1") (pin "2") (pinfunction "2_2") (pintype "passive"))
      (node (ref "VIN1") (pin "2") (pinfunction "2_2") (pintype "passive"))
    )
    (net (code "88") (name "Net-(U1-*RST)") (class "Default")
      (node (ref "R1") (pin "1") (pinfunction "1_1") (pintype "passive"))
      (node (ref "U1") (pin "9") (pinfunction "*RST_9") (pintype "passive"))
    )
    (net (code "89") (name "Net-(U3-AD0)") (class "Default")
      (node (ref "R11") (pin "2") (pinfunction "2_2") (pintype "passive"))
      (node (ref "U3") (pin "9") (pinfunction "AD0_9") (pintype "passive"))
    )
    (net (code "90") (name "Net-(U3-CPOUT)") (class "Default")
      (node (ref "C7") (pin "1") (pinfunction "1_1") (pintype "passive"))
      (node (ref "U3") (pin "20") (pinfunction "CPOUT_20") (pintype "passive"))
    )
    (net (code "91") (name "Net-(U3-REGOUT)") (class "Default")
      (node (ref "C6") (pin "2") (pinfunction "2_2") (pintype "passive"))
      (node (ref "U3") (pin "10") (pinfunction "REGOUT_10") (pintype "passive"))
    )
    (net (code "92") (name "Net-(USB1-CC1)") (class "Default")
      (node (ref "R2") (pin "2") (pinfunction "2_2") (pintype "passive"))
      (node (ref "USB1") (pin "A5") (pinfunction "CC1_A5") (pintype "passive"))
    )
    (net (code "93") (name "Net-(USB1-CC2)") (class "Default")
      (node (ref "R3") (pin "2") (pinfunction "2_2") (pintype "passive"))
      (node (ref "USB1") (pin "B5") (pinfunction "CC2_B5") (pintype "passive"))
    )
    (net (code "94") (name "USB_5V") (class "Default")
      (node (ref "F1") (pin "1") (pinfunction "1_1") (pintype "passive"))
      (node (ref "R1") (pin "2") (pinfunction "2_2") (pintype "passive"))
      (node (ref "TP_USB_5V") (pin "1") (pinfunction "1_1") (pintype "passive"))
      (node (ref "U1") (pin "7") (pinfunction "REGIN_7") (pintype "passive"))
      (node (ref "U1") (pin "8") (pinfunction "VBUS_8") (pintype "passive"))
      (node (ref "USB1") (pin "A4") (pinfunction "VBUS_A4") (pintype "passive"))
      (node (ref "USB1") (pin "A9") (pinfunction "VBUS_A9") (pintype "passive"))
      (node (ref "USB1") (pin "B4") (pinfunction "VBUS_B4") (pintype "passive"))
      (node (ref "USB1") (pin "B9") (pinfunction "VBUS_B9") (pintype "passive"))
    )
    (net (code "95") (name "VCC3V3") (class "Default")
      (node (ref "AMS1") (pin "2") (pinfunction "Vout_2") (pintype "passive"))
      (node (ref "AMS1") (pin "4") (pinfunction "Vout_4") (pintype "passive"))
      (node (ref "C21") (pin "2") (pinfunction "2_2") (pintype "passive"))
      (node (ref "C22") (pin "2") (pinfunction "2_2") (pintype "passive"))
      (node (ref "C23") (pin "2") (pinfunction "2_2") (pintype "passive"))
      (node (ref "C24") (pin "2") (pinfunction "2_2") (pintype "passive"))
      (node (ref "C25") (pin "2") (pinfunction "2_2") (pintype "passive"))
      (node (ref "C26") (pin "2") (pinfunction "2_2") (pintype "passive"))
      (node (ref "C3") (pin "2") (pinfunction "2_2") (pintype "passive"))
      (node (ref "C4") (pin "2") (pinfunction "2_2") (pintype "passive"))
      (node (ref "C5") (pin "2") (pinfunction "2_2") (pintype "passive"))
      (node (ref "C8") (pin "1") (pinfunction "1_1") (pintype "passive"))
      (node (ref "JP2") (pin "1") (pinfunction "1_1") (pintype "passive"))
      (node (ref "JP2") (pin "2") (pinfunction "2_2") (pintype "passive"))
      (node (ref "JP2") (pin "3") (pinfunction "3_3") (pintype "passive"))
      (node (ref "JP2") (pin "4") (pinfunction "4_4") (pintype "passive"))
      (node (ref "JP2") (pin "5") (pinfunction "5_5") (pintype "passive"))
      (node (ref "JP_SWD") (pin "1") (pinfunction "1_1") (pintype "passive"))
      (node (ref "Q2") (pin "2") (pinfunction "E_2") (pintype "passive"))
      (node (ref "R10") (pin "2") (pinfunction "2_2") (pintype "passive"))
      (node (ref "R14") (pin "2") (pinfunction "2_2") (pintype "passive"))
      (node (ref "R15") (pin "2") (pinfunction "2_2") (pintype "passive"))
      (node (ref "R16") (pin "2") (pinfunction "2_2") (pintype "passive"))
      (node (ref "R17") (pin "2") (pinfunction "2_2") (pintype "passive"))
      (node (ref "R4") (pin "1") (pinfunction "1_1") (pintype "passive"))
      (node (ref "R8") (pin "2") (pinfunction "2_2") (pintype "passive"))
      (node (ref "TP_VCC3V3") (pin "1") (pinfunction "1_1") (pintype "passive"))
      (node (ref "U2") (pin "1") (pinfunction "VBAT_1") (pintype "power_in"))
      (node (ref "U2") (pin "13") (pinfunction "VDDA_13") (pintype "power_in"))
      (node (ref "U2") (pin "19") (pinfunction "VDD_4_19") (pintype "power_in"))
      (node (ref "U2") (pin "32") (pinfunction "VDD_1_32") (pintype "power_in"))
      (node (ref "U2") (pin "48") (pinfunction "VDD_2_48") (pintype "power_in"))
      (node (ref "U2") (pin "64") (pinfunction "VDD_3_64") (pintype "power_in"))
      (node (ref "U3") (pin "13") (pinfunction "VDD_13") (pintype "passive"))
      (node (ref "U3") (pin "8") (pinfunction "VLogic_8") (pintype "passive"))
      (node (ref "U6") (pin "3") (pinfunction "VCC_3") (pintype "passive"))
    )
    (net (code "96") (name "VCC5V") (class "Default")
      (node (ref "AMS1") (pin "3") (pinfunction "Vin_3") (pintype "passive"))
      (node (ref "C1") (pin "2") (pinfunction "2_2") (pintype "passive"))
      (node (ref "C17") (pin "1") (pinfunction "1_1") (pintype "passive"))
      (node (ref "C18") (pin "2") (pinfunction "2_2") (pintype "passive"))
      (node (ref "C19") (pin "1") (pinfunction "1_1") (pintype "passive"))
      (node (ref "C2") (pin "2") (pinfunction "2_2") (pintype "passive"))
      (node (ref "C20") (pin "2") (pinfunction "2_2") (pintype "passive"))
      (node (ref "C27") (pin "2") (pinfunction "2_2") (pintype "passive"))
      (node (ref "C31") (pin "2") (pinfunction "2_2") (pintype "passive"))
      (node (ref "C32") (pin "2") (pinfunction "2_2") (pintype "passive"))
      (node (ref "EM1") (pin "2") (pinfunction "2_2") (pintype "passive"))
      (node (ref "EM2") (pin "2") (pinfunction "2_2") (pintype "passive"))
      (node (ref "EM3") (pin "2") (pinfunction "2_2") (pintype "passive"))
      (node (ref "EM4") (pin "2") (pinfunction "2_2") (pintype "passive"))
      (node (ref "F1") (pin "2") (pinfunction "2_2") (pintype "passive"))
      (node (ref "JP1") (pin "1") (pinfunction "1_1") (pintype "passive"))
      (node (ref "JP1") (pin "2") (pinfunction "2_2") (pintype "passive"))
      (node (ref "JP1") (pin "3") (pinfunction "3_3") (pintype "passive"))
      (node (ref "JP1") (pin "4") (pinfunction "4_4") (pintype "passive"))
      (node (ref "JP1") (pin "5") (pinfunction "5_5") (pintype "passive"))
      (node (ref "JP_PI") (pin "1") (pinfunction "1_1") (pintype "passive"))
      (node (ref "L1") (pin "1") (pinfunction "1_1") (pintype "passive"))
      (node (ref "R20") (pin "1") (pinfunction "1_1") (pintype "passive"))
      (node (ref "RP12") (pin "5") (pinfunction "5_5") (pintype "passive"))
      (node (ref "RP12") (pin "6") (pinfunction "6_6") (pintype "passive"))
      (node (ref "RP12") (pin "7") (pinfunction "7_7") (pintype "passive"))
      (node (ref "RP12") (pin "8") (pinfunction "8_8") (pintype "passive"))
      (node (ref "RP34") (pin "5") (pinfunction "5_5") (pintype "passive"))
      (node (ref "RP34") (pin "6") (pinfunction "6_6") (pintype "passive"))
      (node (ref "RP34") (pin "7") (pinfunction "7_7") (pintype "passive"))
      (node (ref "RP34") (pin "8") (pinfunction "8_8") (pintype "passive"))
      (node (ref "TP_VCC5V") (pin "1") (pinfunction "1_1") (pintype "passive"))
      (node (ref "U4") (pin "19") (pinfunction "STBY_19") (pintype "passive"))
      (node (ref "U4") (pin "20") (pinfunction "VCC_20") (pintype "passive"))
      (node (ref "U5") (pin "19") (pinfunction "STBY_19") (pintype "passive"))
      (node (ref "U5") (pin "20") (pinfunction "VCC_20") (pintype "passive"))
    )
    (net (code "97") (name "VCC12V") (class "Default")
      (node (ref "C13") (pin "2") (pinfunction "2_2") (pintype "passive"))
      (node (ref "C14") (pin "2") (pinfunction "2_2") (pintype "passive"))
      (node (ref "C15") (pin "2") (pinfunction "2_2") (pintype "passive"))
      (node (ref "C16") (pin "2") (pinfunction "2_2") (pintype "passive"))
      (node (ref "C28") (pin "2") (pinfunction "2_2") (pintype "passive"))
      (node (ref "C29") (pin "2") (pinfunction "2_2") (pintype "passive"))
      (node (ref "MP1") (pin "2") (pinfunction "IN_2") (pintype "passive"))
      (node (ref "R18") (pin "2") (pinfunction "2_2") (pintype "passive"))
      (node (ref "R22") (pin "2") (pinfunction "2_2") (pintype "passive"))
      (node (ref "S1") (pin "3") (pinfunction "3_3") (pintype "passive"))
      (node (ref "TP_VCC12V") (pin "1") (pinfunction "1_1") (pintype "passive"))
      (node (ref "U4") (pin "13") (pinfunction "VM2_13") (pintype "passive"))
      (node (ref "U4") (pin "14") (pinfunction "VM3_14") (pintype "passive"))
      (node (ref "U4") (pin "24") (pinfunction "VM1_24") (pintype "passive"))
      (node (ref "U5") (pin "13") (pinfunction "VM2_13") (pintype "passive"))
      (node (ref "U5") (pin "14") (pinfunction "VM3_14") (pintype "passive"))
      (node (ref "U5") (pin "24") (pinfunction "VM1_24") (pintype "passive"))
    )
    (net (code "98") (name "unconnected-(S1-Pad1)") (class "Default")
      (node (ref "S1") (pin "1") (pinfunction "1_1") (pintype "passive"))
    )
    (net (code "99") (name "unconnected-(U1-*SUSPEND-Pad11)") (class "Default")
      (node (ref "U1") (pin "11") (pinfunction "*SUSPEND_11") (pintype "passive"))
    )
    (net (code "100") (name "unconnected-(U1-CTS-Pad23)") (class "Default")
      (node (ref "U1") (pin "23") (pinfunction "CTS_23") (pintype "passive"))
    )
    (net (code "101") (name "unconnected-(U1-DCD-Pad1)") (class "Default")
      (node (ref "U1") (pin "1") (pinfunction "DCD_1") (pintype "passive"))
    )
    (net (code "102") (name "unconnected-(U1-DSR-Pad27)") (class "Default")
      (node (ref "U1") (pin "27") (pinfunction "DSR_27") (pintype "passive"))
    )
    (net (code "103") (name "unconnected-(U1-NC-Pad10)") (class "Default")
      (node (ref "U1") (pin "10") (pinfunction "NC_10") (pintype "passive"))
    )
    (net (code "104") (name "unconnected-(U1-NC-Pad13)") (class "Default")
      (node (ref "U1") (pin "13") (pinfunction "NC_13") (pintype "passive"))
    )
    (net (code "105") (name "unconnected-(U1-NC-Pad14)") (class "Default")
      (node (ref "U1") (pin "14") (pinfunction "NC_14") (pintype "passive"))
    )
    (net (code "106") (name "unconnected-(U1-NC-Pad15)") (class "Default")
      (node (ref "U1") (pin "15") (pinfunction "NC_15") (pintype "passive"))
    )
    (net (code "107") (name "unconnected-(U1-NC-Pad16)") (class "Default")
      (node (ref "U1") (pin "16") (pinfunction "NC_16") (pintype "passive"))
    )
    (net (code "108") (name "unconnected-(U1-NC-Pad17)") (class "Default")
      (node (ref "U1") (pin "17") (pinfunction "NC_17") (pintype "passive"))
    )
    (net (code "109") (name "unconnected-(U1-NC-Pad18)") (class "Default")
      (node (ref "U1") (pin "18") (pinfunction "NC_18") (pintype "passive"))
    )
    (net (code "110") (name "unconnected-(U1-NC-Pad19)") (class "Default")
      (node (ref "U1") (pin "19") (pinfunction "NC_19") (pintype "passive"))
    )
    (net (code "111") (name "unconnected-(U1-NC-Pad20)") (class "Default")
      (node (ref "U1") (pin "20") (pinfunction "NC_20") (pintype "passive"))
    )
    (net (code "112") (name "unconnected-(U1-NC-Pad21)") (class "Default")
      (node (ref "U1") (pin "21") (pinfunction "NC_21") (pintype "passive"))
    )
    (net (code "113") (name "unconnected-(U1-NC-Pad22)") (class "Default")
      (node (ref "U1") (pin "22") (pinfunction "NC_22") (pintype "passive"))
    )
    (net (code "114") (name "unconnected-(U1-RI-Pad2)") (class "Default")
      (node (ref "U1") (pin "2") (pinfunction "RI_2") (pintype "passive"))
    )
    (net (code "115") (name "unconnected-(U1-SUSPEND-Pad12)") (class "Default")
      (node (ref "U1") (pin "12") (pinfunction "SUSPEND_12") (pintype "passive"))
    )
    (net (code "116") (name "unconnected-(U1-VDD-Pad6)") (class "Default")
      (node (ref "U1") (pin "6") (pinfunction "VDD_6") (pintype "passive"))
    )
    (net (code "117") (name "unconnected-(U3-A_CL-Pad7)") (class "Default")
      (node (ref "U3") (pin "7") (pinfunction "A_CL_7") (pintype "passive+no_connect"))
    )
    (net (code "118") (name "unconnected-(U3-A_DA-Pad6)") (class "Default")
      (node (ref "U3") (pin "6") (pinfunction "A_DA_6") (pintype "passive+no_connect"))
    )
    (net (code "119") (name "unconnected-(U3-CLKOUT-Pad22)") (class "Default")
      (node (ref "U3") (pin "22") (pinfunction "CLKOUT_22") (pintype "passive+no_connect"))
    )
    (net (code "120") (name "unconnected-(U3-NC-Pad2)") (class "Default")
      (node (ref "U3") (pin "2") (pinfunction "NC_2") (pintype "passive+no_connect"))
    )
    (net (code "121") (name "unconnected-(U3-NC-Pad3)") (class "Default")
      (node (ref "U3") (pin "3") (pinfunction "NC_3") (pintype "passive+no_connect"))
    )
    (net (code "122") (name "unconnected-(U3-NC-Pad4)") (class "Default")
      (node (ref "U3") (pin "4") (pinfunction "NC_4") (pintype "passive+no_connect"))
    )
    (net (code "123") (name "unconnected-(U3-NC-Pad5)") (class "Default")
      (node (ref "U3") (pin "5") (pinfunction "NC_5") (pintype "passive+no_connect"))
    )
    (net (code "124") (name "unconnected-(U3-NC-Pad14)") (class "Default")
      (node (ref "U3") (pin "14") (pinfunction "NC_14") (pintype "passive"))
    )
    (net (code "125") (name "unconnected-(U3-NC-Pad15)") (class "Default")
      (node (ref "U3") (pin "15") (pinfunction "NC_15") (pintype "passive"))
    )
    (net (code "126") (name "unconnected-(U3-NC-Pad16)") (class "Default")
      (node (ref "U3") (pin "16") (pinfunction "NC_16") (pintype "passive"))
    )
    (net (code "127") (name "unconnected-(U3-NC-Pad17)") (class "Default")
      (node (ref "U3") (pin "17") (pinfunction "NC_17") (pintype "passive"))
    )
    (net (code "128") (name "unconnected-(U3-RESV-Pad19)") (class "Default")
      (node (ref "U3") (pin "19") (pinfunction "RESV_19") (pintype "passive+no_connect"))
    )
    (net (code "129") (name "unconnected-(U3-RESV-Pad21)") (class "Default")
      (node (ref "U3") (pin "21") (pinfunction "RESV_21") (pintype "passive+no_connect"))
    )
    (net (code "130") (name "unconnected-(U6-NC-Pad5)") (class "Default")
      (node (ref "U6") (pin "5") (pinfunction "NC_5") (pintype "passive"))
    )
    (net (code "131") (name "unconnected-(U6-NC-Pad8)") (class "Default")
      (node (ref "U6") (pin "8") (pinfunction "NC_8") (pintype "passive"))
    )
    (net (code "132") (name "unconnected-(USB1-RX1+-PadB11)") (class "Default")
      (node (ref "USB1") (pin "B11") (pinfunction "RX1+_B11") (pintype "passive"))
    )
    (net (code "133") (name "unconnected-(USB1-RX1--PadB10)") (class "Default")
      (node (ref "USB1") (pin "B10") (pinfunction "RX1-_B10") (pintype "passive"))
    )
    (net (code "134") (name "unconnected-(USB1-RX2+-PadA11)") (class "Default")
      (node (ref "USB1") (pin "A11") (pinfunction "RX2+_A11") (pintype "passive"))
    )
    (net (code "135") (name "unconnected-(USB1-RX2--PadA10)") (class "Default")
      (node (ref "USB1") (pin "A10") (pinfunction "RX2-_A10") (pintype "passive"))
    )
    (net (code "136") (name "unconnected-(USB1-SBU1-PadA8)") (class "Default")
      (node (ref "USB1") (pin "A8") (pinfunction "SBU1_A8") (pintype "passive"))
    )
    (net (code "137") (name "unconnected-(USB1-SBU2-PadB8)") (class "Default")
      (node (ref "USB1") (pin "B8") (pinfunction "SBU2_B8") (pintype "passive"))
    )
    (net (code "138") (name "unconnected-(USB1-TX1+-PadA2)") (class "Default")
      (node (ref "USB1") (pin "A2") (pinfunction "TX1+_A2") (pintype "passive"))
    )
    (net (code "139") (name "unconnected-(USB1-TX1--PadA3)") (class "Default")
      (node (ref "USB1") (pin "A3") (pinfunction "TX1-_A3") (pintype "passive"))
    )
    (net (code "140") (name "unconnected-(USB1-TX2+-PadB2)") (class "Default")
      (node (ref "USB1") (pin "B2") (pinfunction "TX2+_B2") (pintype "passive"))
    )
    (net (code "141") (name "unconnected-(USB1-TX2--PadB3)") (class "Default")
      (node (ref "USB1") (pin "B3") (pinfunction "TX2-_B3") (pintype "passive"))
    )
  )
)
